# W601D.net
KiCad netlist of a schematic drawn in EAGLE
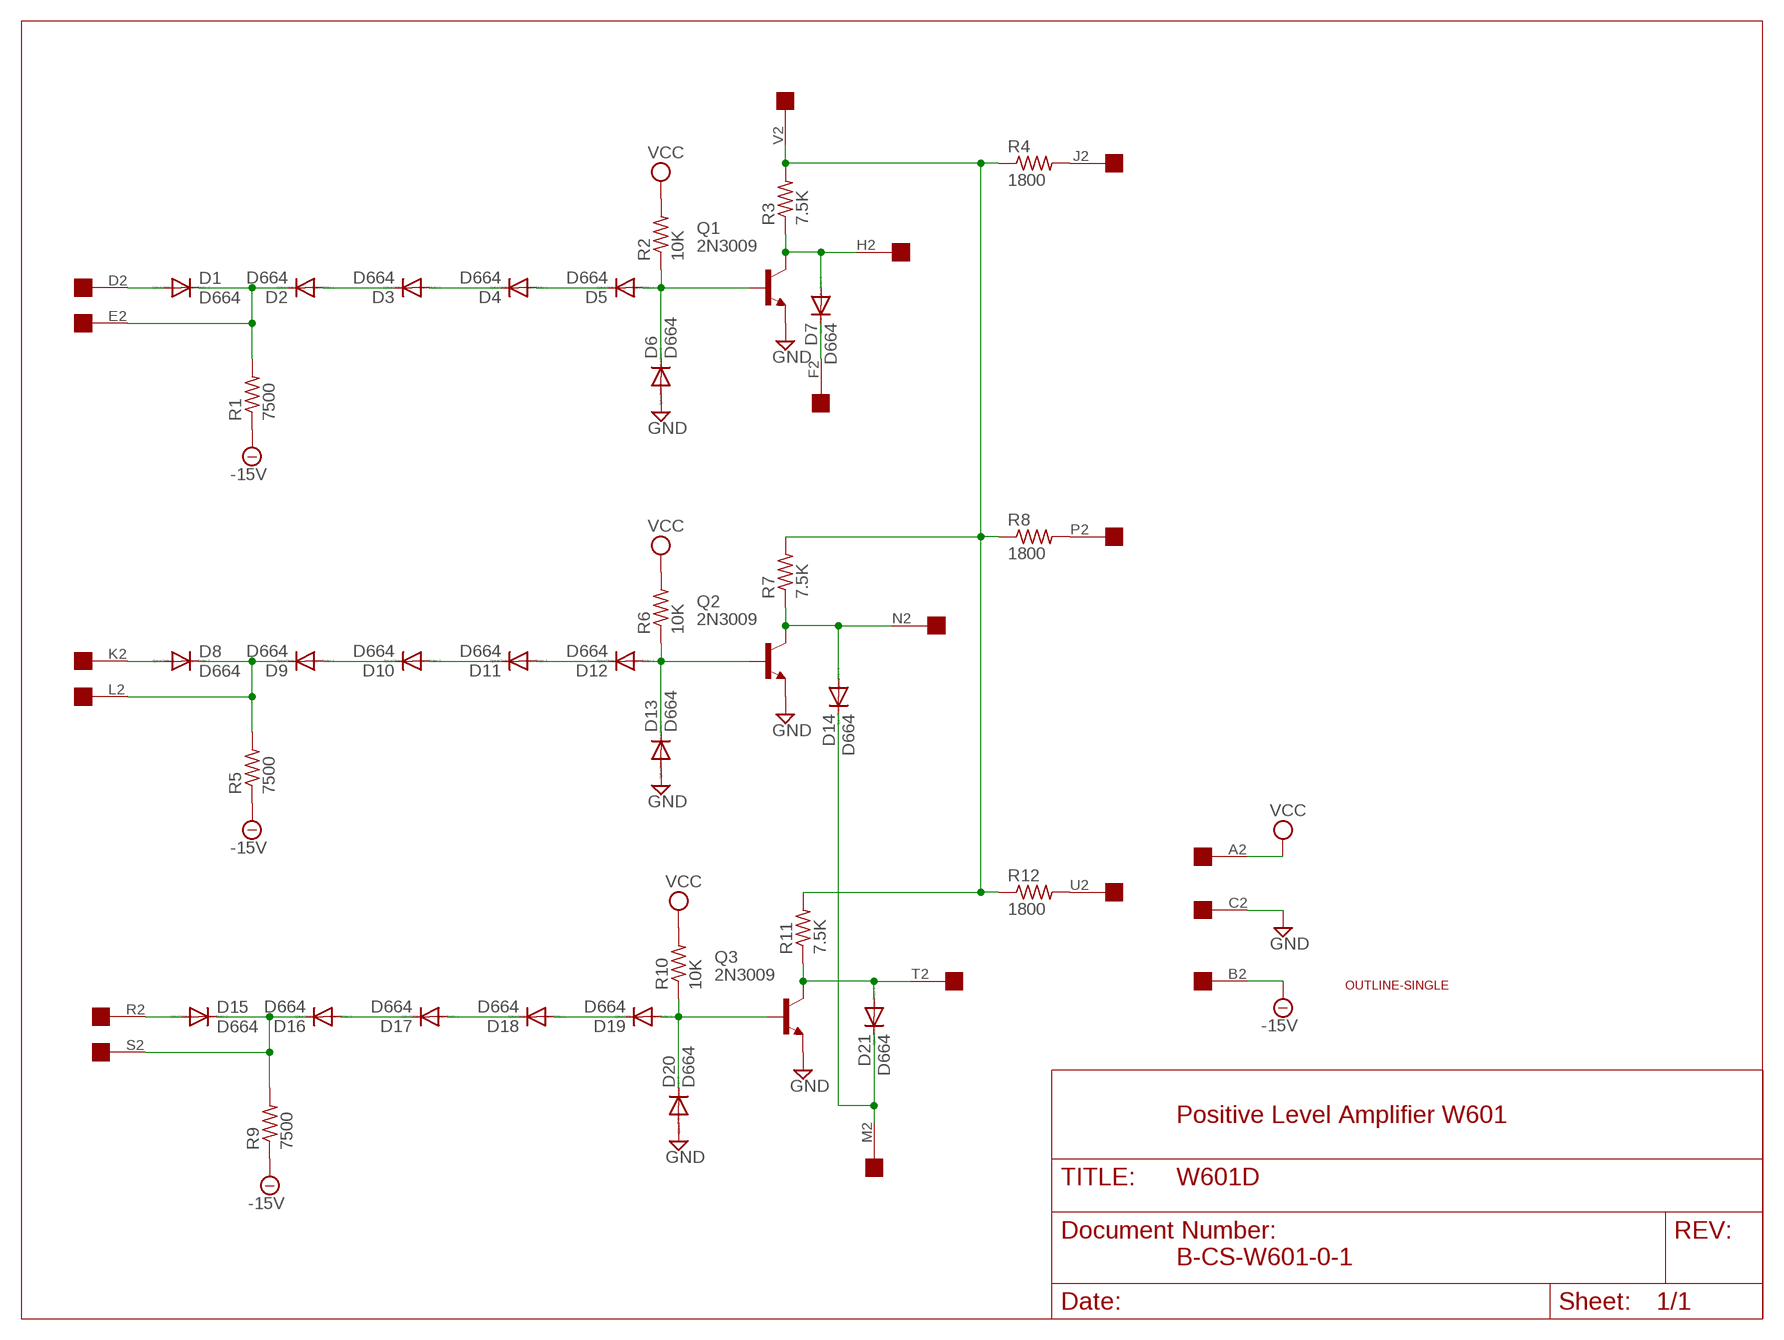
[diagram p0: schematic, sheet 1]

(export (version "E")
  (design (tool "Eeschema 10.0.6"))
  (components
    (comp (ref "D1")
      (value "D664")
      (footprint "eagle-import:DO35-10")
      (libsource (lib "eagle-import") (part "DIODE-DO35-10"))
    )
    (comp (ref "D2")
      (value "D664")
      (footprint "eagle-import:DO35-10")
      (libsource (lib "eagle-import") (part "DIODE-DO35-10"))
    )
    (comp (ref "D3")
      (value "D664")
      (footprint "eagle-import:DO35-10")
      (libsource (lib "eagle-import") (part "DIODE-DO35-10"))
    )
    (comp (ref "D4")
      (value "D664")
      (footprint "eagle-import:DO35-10")
      (libsource (lib "eagle-import") (part "DIODE-DO35-10"))
    )
    (comp (ref "D5")
      (value "D664")
      (footprint "eagle-import:DO35-10")
      (libsource (lib "eagle-import") (part "DIODE-DO35-10"))
    )
    (comp (ref "D6")
      (value "D664")
      (footprint "eagle-import:DO35-10")
      (libsource (lib "eagle-import") (part "DIODE-DO35-10"))
    )
    (comp (ref "D7")
      (value "D664")
      (footprint "eagle-import:DO35-10")
      (libsource (lib "eagle-import") (part "DIODE-DO35-10"))
    )
    (comp (ref "D8")
      (value "D664")
      (footprint "eagle-import:DO35-10")
      (libsource (lib "eagle-import") (part "DIODE-DO35-10"))
    )
    (comp (ref "D9")
      (value "D664")
      (footprint "eagle-import:DO35-10")
      (libsource (lib "eagle-import") (part "DIODE-DO35-10"))
    )
    (comp (ref "D10")
      (value "D664")
      (footprint "eagle-import:DO35-10")
      (libsource (lib "eagle-import") (part "DIODE-DO35-10"))
    )
    (comp (ref "D11")
      (value "D664")
      (footprint "eagle-import:DO35-10")
      (libsource (lib "eagle-import") (part "DIODE-DO35-10"))
    )
    (comp (ref "D12")
      (value "D664")
      (footprint "eagle-import:DO35-10")
      (libsource (lib "eagle-import") (part "DIODE-DO35-10"))
    )
    (comp (ref "D13")
      (value "D664")
      (footprint "eagle-import:DO35-10")
      (libsource (lib "eagle-import") (part "DIODE-DO35-10"))
    )
    (comp (ref "D14")
      (value "D664")
      (footprint "eagle-import:DO35-10")
      (libsource (lib "eagle-import") (part "DIODE-DO35-10"))
    )
    (comp (ref "D15")
      (value "D664")
      (footprint "eagle-import:DO35-10")
      (libsource (lib "eagle-import") (part "DIODE-DO35-10"))
    )
    (comp (ref "D16")
      (value "D664")
      (footprint "eagle-import:DO35-10")
      (libsource (lib "eagle-import") (part "DIODE-DO35-10"))
    )
    (comp (ref "D17")
      (value "D664")
      (footprint "eagle-import:DO35-10")
      (libsource (lib "eagle-import") (part "DIODE-DO35-10"))
    )
    (comp (ref "D18")
      (value "D664")
      (footprint "eagle-import:DO35-10")
      (libsource (lib "eagle-import") (part "DIODE-DO35-10"))
    )
    (comp (ref "D19")
      (value "D664")
      (footprint "eagle-import:DO35-10")
      (libsource (lib "eagle-import") (part "DIODE-DO35-10"))
    )
    (comp (ref "D20")
      (value "D664")
      (footprint "eagle-import:DO35-10")
      (libsource (lib "eagle-import") (part "DIODE-DO35-10"))
    )
    (comp (ref "D21")
      (value "D664")
      (footprint "eagle-import:DO35-10")
      (libsource (lib "eagle-import") (part "DIODE-DO35-10"))
    )
    (comp (ref "Q1")
      (value "2N3009")
      (footprint "eagle-import:TO5")
      (libsource (lib "eagle-import") (part "-NPN-TO5"))
    )
    (comp (ref "Q2")
      (value "2N3009")
      (footprint "eagle-import:TO5")
      (libsource (lib "eagle-import") (part "-NPN-TO5"))
    )
    (comp (ref "Q3")
      (value "2N3009")
      (footprint "eagle-import:TO5")
      (libsource (lib "eagle-import") (part "-NPN-TO5"))
    )
    (comp (ref "R1")
      (value "7500")
      (footprint "eagle-import:0207_10")
      (libsource (lib "eagle-import") (part "R-US_0207/10"))
    )
    (comp (ref "R2")
      (value "10K")
      (footprint "eagle-import:0207_10")
      (libsource (lib "eagle-import") (part "R-US_0207/10"))
    )
    (comp (ref "R3")
      (value "7.5K")
      (footprint "eagle-import:0207_10")
      (libsource (lib "eagle-import") (part "R-US_0207/10"))
    )
    (comp (ref "R4")
      (value "1800")
      (footprint "eagle-import:0207_10")
      (libsource (lib "eagle-import") (part "R-US_0207/10"))
    )
    (comp (ref "R5")
      (value "7500")
      (footprint "eagle-import:0207_10")
      (libsource (lib "eagle-import") (part "R-US_0207/10"))
    )
    (comp (ref "R6")
      (value "10K")
      (footprint "eagle-import:0207_10")
      (libsource (lib "eagle-import") (part "R-US_0207/10"))
    )
    (comp (ref "R7")
      (value "7.5K")
      (footprint "eagle-import:0207_10")
      (libsource (lib "eagle-import") (part "R-US_0207/10"))
    )
    (comp (ref "R8")
      (value "1800")
      (footprint "eagle-import:0207_10")
      (libsource (lib "eagle-import") (part "R-US_0207/10"))
    )
    (comp (ref "R9")
      (value "7500")
      (footprint "eagle-import:0207_10")
      (libsource (lib "eagle-import") (part "R-US_0207/10"))
    )
    (comp (ref "R10")
      (value "10K")
      (footprint "eagle-import:0207_10")
      (libsource (lib "eagle-import") (part "R-US_0207/10"))
    )
    (comp (ref "R11")
      (value "7.5K")
      (footprint "eagle-import:0207_10")
      (libsource (lib "eagle-import") (part "R-US_0207/10"))
    )
    (comp (ref "R12")
      (value "1800")
      (footprint "eagle-import:0207_10")
      (libsource (lib "eagle-import") (part "R-US_0207/10"))
    )
    (comp (ref "U$1")
      (value "OUTLINE-SINGLE")
      (footprint "eagle-import:SINGLE")
      (libsource (lib "eagle-import") (part "OUTLINE-SINGLE"))
    )
    (comp (ref "U$2")
      (value "EDGE-1")
      (footprint "eagle-import:EDGE-CON1")
      (libsource (lib "eagle-import") (part "EDGE-1"))
    )
  )
  (nets
    (net (code "1") (name "-15V") (class "Default")
      (node (ref "R1") (pin "1") (pinfunction "1_1") (pintype "passive"))
      (node (ref "R5") (pin "1") (pinfunction "1_1") (pintype "passive"))
      (node (ref "R9") (pin "1") (pinfunction "1_1") (pintype "passive"))
      (node (ref "U$2") (pin "B2") (pinfunction "1_B2") (pintype "bidirectional"))
    )
    (net (code "2") (name "GND") (class "Default")
      (node (ref "D13") (pin "A") (pinfunction "A_A") (pintype "passive"))
      (node (ref "D20") (pin "A") (pinfunction "A_A") (pintype "passive"))
      (node (ref "D6") (pin "A") (pinfunction "A_A") (pintype "passive"))
      (node (ref "Q1") (pin "1") (pinfunction "E_1") (pintype "passive"))
      (node (ref "Q2") (pin "1") (pinfunction "E_1") (pintype "passive"))
      (node (ref "Q3") (pin "1") (pinfunction "E_1") (pintype "passive"))
      (node (ref "U$2") (pin "C2") (pinfunction "1_C2") (pintype "bidirectional"))
    )
    (net (code "3") (name "Net-(D2-PadA)") (class "Default")
      (node (ref "D2") (pin "A") (pinfunction "A_A") (pintype "passive"))
      (node (ref "D3") (pin "C") (pinfunction "C_C") (pintype "passive"))
    )
    (net (code "4") (name "Net-(D3-PadA)") (class "Default")
      (node (ref "D3") (pin "A") (pinfunction "A_A") (pintype "passive"))
      (node (ref "D4") (pin "C") (pinfunction "C_C") (pintype "passive"))
    )
    (net (code "5") (name "Net-(D4-PadA)") (class "Default")
      (node (ref "D4") (pin "A") (pinfunction "A_A") (pintype "passive"))
      (node (ref "D5") (pin "C") (pinfunction "C_C") (pintype "passive"))
    )
    (net (code "6") (name "Net-(D10-PadA)") (class "Default")
      (node (ref "D10") (pin "A") (pinfunction "A_A") (pintype "passive"))
      (node (ref "D11") (pin "C") (pinfunction "C_C") (pintype "passive"))
    )
    (net (code "7") (name "Net-(D10-PadC)") (class "Default")
      (node (ref "D10") (pin "C") (pinfunction "C_C") (pintype "passive"))
      (node (ref "D9") (pin "A") (pinfunction "A_A") (pintype "passive"))
    )
    (net (code "8") (name "Net-(D11-PadA)") (class "Default")
      (node (ref "D11") (pin "A") (pinfunction "A_A") (pintype "passive"))
      (node (ref "D12") (pin "C") (pinfunction "C_C") (pintype "passive"))
    )
    (net (code "9") (name "Net-(D16-PadA)") (class "Default")
      (node (ref "D16") (pin "A") (pinfunction "A_A") (pintype "passive"))
      (node (ref "D17") (pin "C") (pinfunction "C_C") (pintype "passive"))
    )
    (net (code "10") (name "Net-(D17-PadA)") (class "Default")
      (node (ref "D17") (pin "A") (pinfunction "A_A") (pintype "passive"))
      (node (ref "D18") (pin "C") (pinfunction "C_C") (pintype "passive"))
    )
    (net (code "11") (name "Net-(D18-PadA)") (class "Default")
      (node (ref "D18") (pin "A") (pinfunction "A_A") (pintype "passive"))
      (node (ref "D19") (pin "C") (pinfunction "C_C") (pintype "passive"))
    )
    (net (code "12") (name "Net-(Q1-B)") (class "Default")
      (node (ref "D5") (pin "A") (pinfunction "A_A") (pintype "passive"))
      (node (ref "D6") (pin "C") (pinfunction "C_C") (pintype "passive"))
      (node (ref "Q1") (pin "2") (pinfunction "B_2") (pintype "passive"))
      (node (ref "R2") (pin "1") (pinfunction "1_1") (pintype "passive"))
    )
    (net (code "13") (name "Net-(Q1-C)") (class "Default")
      (node (ref "D7") (pin "A") (pinfunction "A_A") (pintype "passive"))
      (node (ref "Q1") (pin "3") (pinfunction "C_3") (pintype "passive"))
      (node (ref "R3") (pin "1") (pinfunction "1_1") (pintype "passive"))
      (node (ref "U$2") (pin "H2") (pinfunction "1_H2") (pintype "bidirectional"))
    )
    (net (code "14") (name "Net-(Q2-B)") (class "Default")
      (node (ref "D12") (pin "A") (pinfunction "A_A") (pintype "passive"))
      (node (ref "D13") (pin "C") (pinfunction "C_C") (pintype "passive"))
      (node (ref "Q2") (pin "2") (pinfunction "B_2") (pintype "passive"))
      (node (ref "R6") (pin "1") (pinfunction "1_1") (pintype "passive"))
    )
    (net (code "15") (name "Net-(Q2-C)") (class "Default")
      (node (ref "D14") (pin "A") (pinfunction "A_A") (pintype "passive"))
      (node (ref "Q2") (pin "3") (pinfunction "C_3") (pintype "passive"))
      (node (ref "R7") (pin "1") (pinfunction "1_1") (pintype "passive"))
      (node (ref "U$2") (pin "N2") (pinfunction "1_N2") (pintype "bidirectional"))
    )
    (net (code "16") (name "Net-(Q3-B)") (class "Default")
      (node (ref "D19") (pin "A") (pinfunction "A_A") (pintype "passive"))
      (node (ref "D20") (pin "C") (pinfunction "C_C") (pintype "passive"))
      (node (ref "Q3") (pin "2") (pinfunction "B_2") (pintype "passive"))
      (node (ref "R10") (pin "1") (pinfunction "1_1") (pintype "passive"))
    )
    (net (code "17") (name "Net-(Q3-C)") (class "Default")
      (node (ref "D21") (pin "A") (pinfunction "A_A") (pintype "passive"))
      (node (ref "Q3") (pin "3") (pinfunction "C_3") (pintype "passive"))
      (node (ref "R11") (pin "1") (pinfunction "1_1") (pintype "passive"))
      (node (ref "U$2") (pin "T2") (pinfunction "1_T2") (pintype "bidirectional"))
    )
    (net (code "18") (name "Net-(U$2D-1)") (class "Default")
      (node (ref "D1") (pin "A") (pinfunction "A_A") (pintype "passive"))
      (node (ref "U$2") (pin "D2") (pinfunction "1_D2") (pintype "bidirectional"))
    )
    (net (code "19") (name "Net-(U$2E-1)") (class "Default")
      (node (ref "D1") (pin "C") (pinfunction "C_C") (pintype "passive"))
      (node (ref "D2") (pin "C") (pinfunction "C_C") (pintype "passive"))
      (node (ref "R1") (pin "2") (pinfunction "2_2") (pintype "passive"))
      (node (ref "U$2") (pin "E2") (pinfunction "1_E2") (pintype "bidirectional"))
    )
    (net (code "20") (name "Net-(U$2F-1)") (class "Default")
      (node (ref "D7") (pin "C") (pinfunction "C_C") (pintype "passive"))
      (node (ref "U$2") (pin "F2") (pinfunction "1_F2") (pintype "bidirectional"))
    )
    (net (code "21") (name "Net-(U$2H-1)") (class "Default")
      (node (ref "R4") (pin "2") (pinfunction "2_2") (pintype "passive"))
      (node (ref "U$2") (pin "J2") (pinfunction "1_J2") (pintype "bidirectional"))
    )
    (net (code "22") (name "Net-(U$2I-1)") (class "Default")
      (node (ref "D8") (pin "A") (pinfunction "A_A") (pintype "passive"))
      (node (ref "U$2") (pin "K2") (pinfunction "1_K2") (pintype "bidirectional"))
    )
    (net (code "23") (name "Net-(U$2J-1)") (class "Default")
      (node (ref "D8") (pin "C") (pinfunction "C_C") (pintype "passive"))
      (node (ref "D9") (pin "C") (pinfunction "C_C") (pintype "passive"))
      (node (ref "R5") (pin "2") (pinfunction "2_2") (pintype "passive"))
      (node (ref "U$2") (pin "L2") (pinfunction "1_L2") (pintype "bidirectional"))
    )
    (net (code "24") (name "Net-(U$2K-1)") (class "Default")
      (node (ref "D14") (pin "C") (pinfunction "C_C") (pintype "passive"))
      (node (ref "D21") (pin "C") (pinfunction "C_C") (pintype "passive"))
      (node (ref "U$2") (pin "M2") (pinfunction "1_M2") (pintype "bidirectional"))
    )
    (net (code "25") (name "Net-(U$2M-1)") (class "Default")
      (node (ref "R8") (pin "2") (pinfunction "2_2") (pintype "passive"))
      (node (ref "U$2") (pin "P2") (pinfunction "1_P2") (pintype "bidirectional"))
    )
    (net (code "26") (name "Net-(U$2N-1)") (class "Default")
      (node (ref "D15") (pin "A") (pinfunction "A_A") (pintype "passive"))
      (node (ref "U$2") (pin "R2") (pinfunction "1_R2") (pintype "bidirectional"))
    )
    (net (code "27") (name "Net-(U$2O-1)") (class "Default")
      (node (ref "D15") (pin "C") (pinfunction "C_C") (pintype "passive"))
      (node (ref "D16") (pin "C") (pinfunction "C_C") (pintype "passive"))
      (node (ref "R9") (pin "2") (pinfunction "2_2") (pintype "passive"))
      (node (ref "U$2") (pin "S2") (pinfunction "1_S2") (pintype "bidirectional"))
    )
    (net (code "28") (name "Net-(U$2Q-1)") (class "Default")
      (node (ref "R12") (pin "2") (pinfunction "2_2") (pintype "passive"))
      (node (ref "U$2") (pin "U2") (pinfunction "1_U2") (pintype "bidirectional"))
    )
    (net (code "29") (name "Net-(U$2R-1)") (class "Default")
      (node (ref "R11") (pin "2") (pinfunction "2_2") (pintype "passive"))
      (node (ref "R12") (pin "1") (pinfunction "1_1") (pintype "passive"))
      (node (ref "R3") (pin "2") (pinfunction "2_2") (pintype "passive"))
      (node (ref "R4") (pin "1") (pinfunction "1_1") (pintype "passive"))
      (node (ref "R7") (pin "2") (pinfunction "2_2") (pintype "passive"))
      (node (ref "R8") (pin "1") (pinfunction "1_1") (pintype "passive"))
      (node (ref "U$2") (pin "V2") (pinfunction "1_V2") (pintype "bidirectional"))
    )
    (net (code "30") (name "VCC") (class "Default")
      (node (ref "R10") (pin "2") (pinfunction "2_2") (pintype "passive"))
      (node (ref "R2") (pin "2") (pinfunction "2_2") (pintype "passive"))
      (node (ref "R6") (pin "2") (pinfunction "2_2") (pintype "passive"))
      (node (ref "U$2") (pin "A2") (pinfunction "1_A2") (pintype "bidirectional"))
    )
  )
)
